# Buzzor.net
KiCad netlist of a schematic drawn in Altium Designer
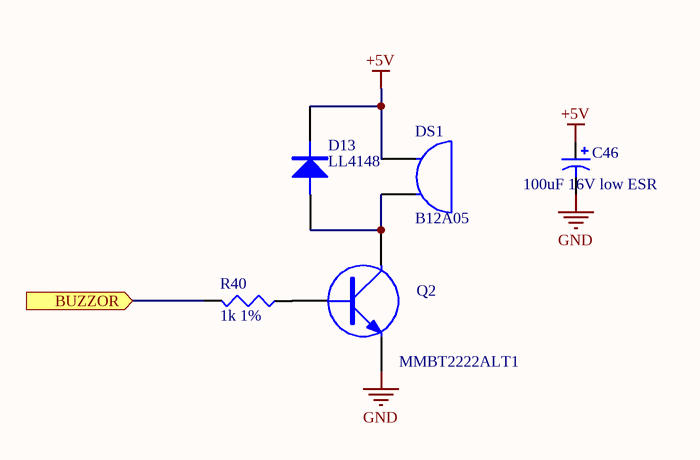
[diagram p0: Buzzor.SchDoc]

(export (version "E")
  (design (tool "Eeschema 10.0.6"))
  (components
    (comp (ref "C46")
      (value "100uF 16V low ESR")
      (footprint "Capacitor Polar Radial Cylinder:CAPPR2-5x11")
      (description "Polarized Capacitor (Radial)")
      (libsource (lib "Miscellaneous Devices") (part "Cap Pol1"))
    )
    (comp (ref "D13")
      (value "LL4148")
      (footprint "MELF - Diode:MELF-D3513-1405")
      (description "Diode")
      (libsource (lib "*") (part "DIODE"))
    )
    (comp (ref "DS1")
      (value "B12A05")
      (footprint "UserPcbLib:BZ12/10mm")
      (description "HXD 5VDC dia12 h10")
      (libsource (lib "*") (part "BUZZER"))
    )
    (comp (ref "Q2")
      (value "MMBT2222ALT1")
      (footprint "SOT23_N:SOT23-3N")
      (description "NPN transistor")
      (libsource (lib "*") (part "NPN"))
    )
    (comp (ref "R40")
      (value "1k 1%")
      (footprint "IPC-7352 Chip_Resistor_N:RESC2012N")
      (description "Resistor")
      (libsource (lib "Miscellaneous Devices") (part "Res3"))
    )
  )
  (nets
    (net (code "1") (name "+5V") (class "Default")
      (node (ref "C46") (pin "1") (pinfunction "1_1") (pintype "passive"))
      (node (ref "D13") (pin "2") (pinfunction "K_2") (pintype "passive"))
      (node (ref "DS1") (pin "1") (pinfunction "A_1") (pintype "passive"))
    )
    (net (code "2") (name "/BUZZOR") (class "Default")
      (node (ref "R40") (pin "2") (pinfunction "2_2") (pintype "passive"))
    )
    (net (code "3") (name "GND") (class "Default")
      (node (ref "C46") (pin "2") (pinfunction "2_2") (pintype "passive"))
      (node (ref "Q2") (pin "2") (pinfunction "E_2") (pintype "passive"))
    )
    (net (code "4") (name "Net-(D13-A)") (class "Default")
      (node (ref "D13") (pin "1") (pinfunction "A_1") (pintype "passive"))
      (node (ref "DS1") (pin "2") (pinfunction "B_2") (pintype "passive"))
      (node (ref "Q2") (pin "3") (pinfunction "C_3") (pintype "passive"))
    )
    (net (code "5") (name "Net-(Q2-B)") (class "Default")
      (node (ref "Q2") (pin "1") (pinfunction "B_1") (pintype "passive"))
      (node (ref "R40") (pin "1") (pinfunction "1_1") (pintype "passive"))
    )
  )
)
